# 01_MAIN.net
KiCad netlist of a schematic drawn in Altium Designer
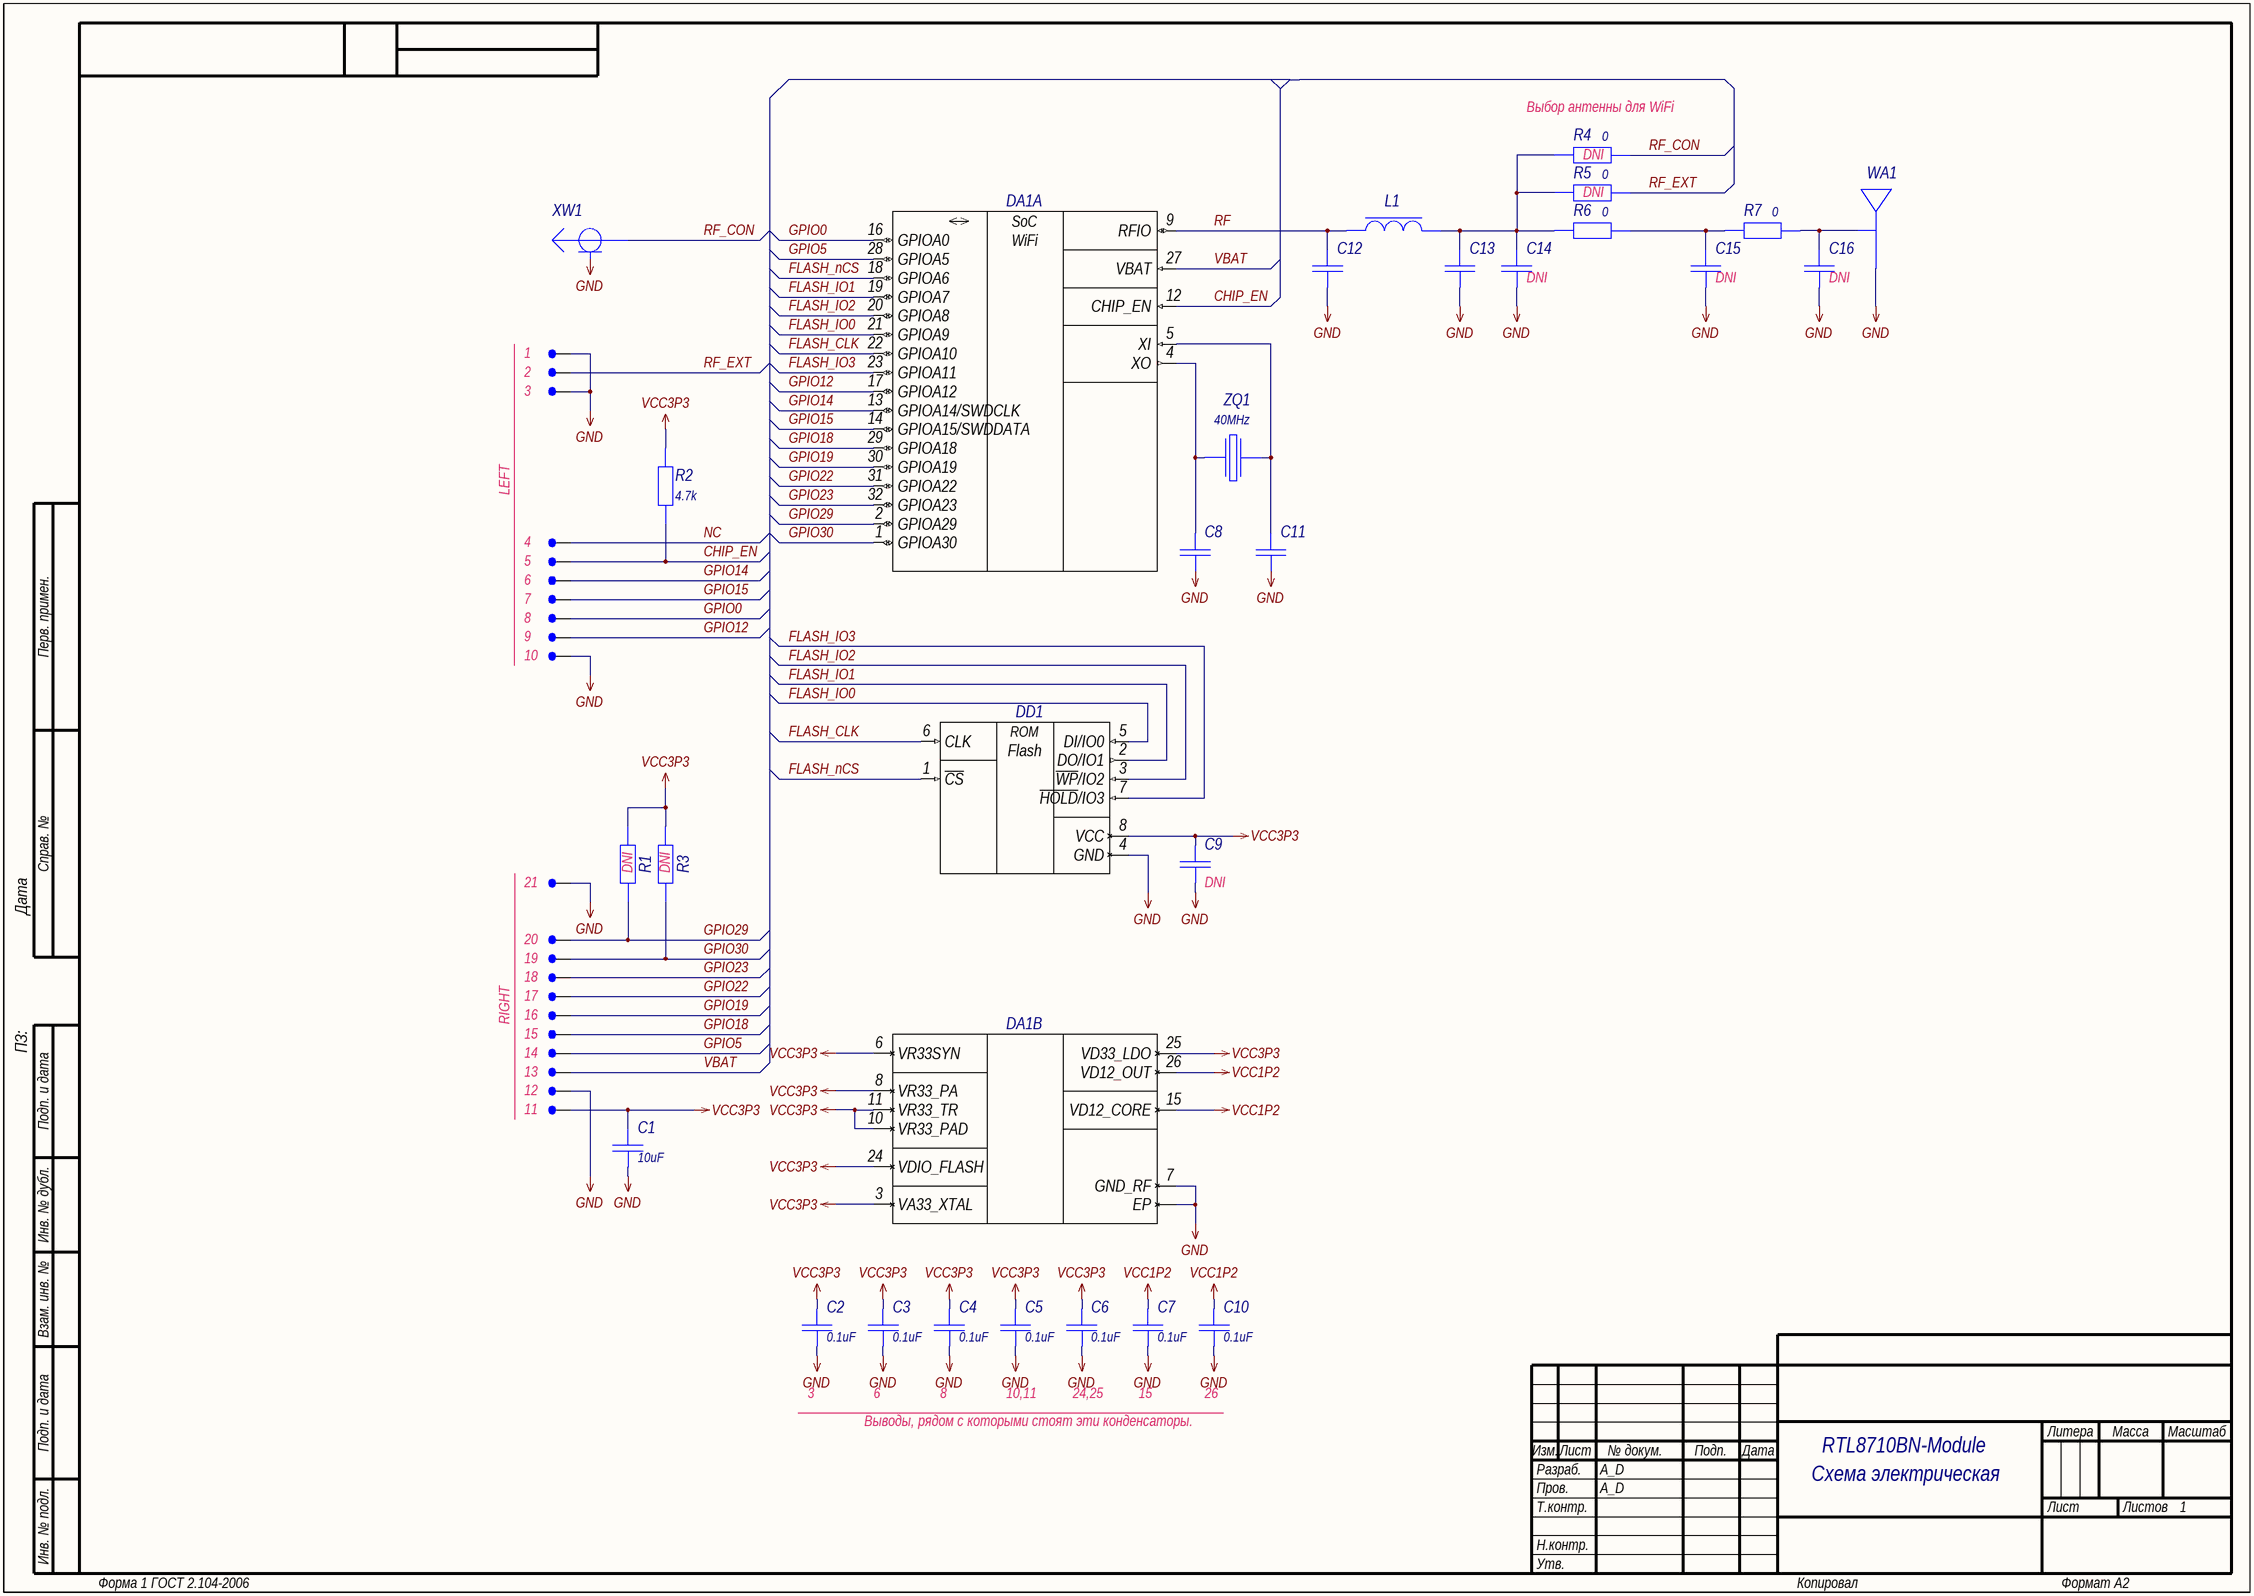
[diagram p0: 01_MAIN.SchDoc]

(export (version "E")
  (design (tool "Eeschema 10.0.6"))
  (components
    (comp (ref "C1")
      (value "10uF")
      (footprint "C0603_L")
      (fields
        (field (name "PART NUMBER") "GRM188R61A106KE69D")
        (field (name "VOLTAGE") "10V")
        (field (name "TOLERANCE") "±10%")
        (field (name "PUBLISHER") "Andrew Danich")
      )
      (libsource (lib "Lib_IMP_GOST") (part "Capacitor"))
    )
    (comp (ref "C2")
      (value "0.1uF")
      (footprint "C0402_L")
      (fields
        (field (name "PART NUMBER") "GRM155R71C104KA88D")
        (field (name "VOLTAGE") "16V")
        (field (name "TOLERANCE") "±10%")
        (field (name "PUBLISHER") "Andrew Danich")
      )
      (libsource (lib "Lib_IMP_GOST") (part "Capacitor"))
    )
    (comp (ref "C3")
      (value "0.1uF")
      (footprint "C0402_L")
      (fields
        (field (name "PART NUMBER") "GRM155R71C104KA88D")
        (field (name "VOLTAGE") "16V")
        (field (name "TOLERANCE") "±10%")
        (field (name "PUBLISHER") "Andrew Danich")
      )
      (libsource (lib "Lib_IMP_GOST") (part "Capacitor"))
    )
    (comp (ref "C4")
      (value "0.1uF")
      (footprint "C0402_L")
      (fields
        (field (name "PART NUMBER") "GRM155R71C104KA88D")
        (field (name "VOLTAGE") "16V")
        (field (name "TOLERANCE") "±10%")
        (field (name "PUBLISHER") "Andrew Danich")
      )
      (libsource (lib "Lib_IMP_GOST") (part "Capacitor"))
    )
    (comp (ref "C5")
      (value "0.1uF")
      (footprint "C0402_L")
      (fields
        (field (name "PART NUMBER") "GRM155R71C104KA88D")
        (field (name "VOLTAGE") "16V")
        (field (name "TOLERANCE") "±10%")
        (field (name "PUBLISHER") "Andrew Danich")
      )
      (libsource (lib "Lib_IMP_GOST") (part "Capacitor"))
    )
    (comp (ref "C6")
      (value "0.1uF")
      (footprint "C0402_L")
      (fields
        (field (name "PART NUMBER") "GRM155R71C104KA88D")
        (field (name "VOLTAGE") "16V")
        (field (name "TOLERANCE") "±10%")
        (field (name "PUBLISHER") "Andrew Danich")
      )
      (libsource (lib "Lib_IMP_GOST") (part "Capacitor"))
    )
    (comp (ref "C7")
      (value "0.1uF")
      (footprint "C0402_L")
      (fields
        (field (name "PART NUMBER") "GRM155R71C104KA88D")
        (field (name "VOLTAGE") "16V")
        (field (name "TOLERANCE") "±10%")
        (field (name "PUBLISHER") "Andrew Danich")
      )
      (libsource (lib "Lib_IMP_GOST") (part "Capacitor"))
    )
    (comp (ref "C8")
      (value "Capacitor")
      (footprint "C0402_L")
      (fields
        (field (name "PART NUMBER") "GRM1555C1H4R0CZ01D")
        (field (name "VOLTAGE") "50V")
        (field (name "TOLERANCE") "±0.25pF")
        (field (name "PUBLISHER") "Andrew Danich")
      )
      (libsource (lib "Lib_IMP_GOST") (part "Capacitor"))
    )
    (comp (ref "C9")
      (value "Capacitor")
      (footprint "C0402_L")
      (fields
        (field (name "PART NUMBER") "GRM155R71C104KA88D")
        (field (name "VOLTAGE") "16V")
        (field (name "TOLERANCE") "±10%")
        (field (name "PUBLISHER") "Andrew Danich")
      )
      (libsource (lib "Lib_IMP_GOST") (part "Capacitor"))
    )
    (comp (ref "C10")
      (value "0.1uF")
      (footprint "C0402_L")
      (fields
        (field (name "PART NUMBER") "GRM155R71C104KA88D")
        (field (name "VOLTAGE") "16V")
        (field (name "TOLERANCE") "±10%")
        (field (name "PUBLISHER") "Andrew Danich")
      )
      (libsource (lib "Lib_IMP_GOST") (part "Capacitor"))
    )
    (comp (ref "C11")
      (value "Capacitor")
      (footprint "C0402_L")
      (fields
        (field (name "PART NUMBER") "GRM1555C1H4R0CZ01D")
        (field (name "VOLTAGE") "50V")
        (field (name "TOLERANCE") "±0.25pF")
        (field (name "PUBLISHER") "Andrew Danich")
      )
      (libsource (lib "Lib_IMP_GOST") (part "Capacitor"))
    )
    (comp (ref "C12")
      (value "Capacitor")
      (footprint "C0402_L")
      (fields
        (field (name "PART NUMBER") "GRM1555C1H100JA01D")
        (field (name "VOLTAGE") "50V")
        (field (name "TOLERANCE") "±5%")
        (field (name "PUBLISHER") "Andrew Danich")
      )
      (libsource (lib "Lib_IMP_GOST") (part "Capacitor"))
    )
    (comp (ref "C13")
      (value "Capacitor")
      (footprint "C0402_L")
      (fields
        (field (name "PART NUMBER") "GRM1555C1H100JA01D")
        (field (name "VOLTAGE") "50V")
        (field (name "TOLERANCE") "±5%")
        (field (name "PUBLISHER") "Andrew Danich")
      )
      (libsource (lib "Lib_IMP_GOST") (part "Capacitor"))
    )
    (comp (ref "C14")
      (value "Capacitor")
      (footprint "C0402_L")
      (fields
        (field (name "PART NUMBER") "GRM1555C1H100JA01D")
        (field (name "VOLTAGE") "50V")
        (field (name "TOLERANCE") "±5%")
        (field (name "PUBLISHER") "Andrew Danich")
      )
      (libsource (lib "Lib_IMP_GOST") (part "Capacitor"))
    )
    (comp (ref "C15")
      (value "Capacitor")
      (footprint "C0402_L")
      (fields
        (field (name "PART NUMBER") "GRM1555C1H100JA01D")
        (field (name "VOLTAGE") "50V")
        (field (name "TOLERANCE") "±5%")
        (field (name "PUBLISHER") "Andrew Danich")
      )
      (libsource (lib "Lib_IMP_GOST") (part "Capacitor"))
    )
    (comp (ref "C16")
      (value "Capacitor")
      (footprint "C0402_L")
      (fields
        (field (name "PART NUMBER") "GRM1555C1H100JA01D")
        (field (name "VOLTAGE") "50V")
        (field (name "TOLERANCE") "±5%")
        (field (name "PUBLISHER") "Andrew Danich")
      )
      (libsource (lib "Lib_IMP_GOST") (part "Capacitor"))
    )
    (comp (ref "DA1")
      (value "RTL8710BN")
      (footprint "QFN-32")
      (fields (field (name "MANUFACTURER") "Realtek") (field (name "PUBLISHER") "Andrew Danich"))
      (libsource (lib "Lib_IMP_GOST") (part "RTL8710BN"))
    )
    (comp (ref "DD1")
      (value "W25Q-Series")
      (footprint "SOIC-8")
      (fields
        (field (name "PART NUMBER") "W25Q16DVSNIG")
        (field (name "MANUFACTURER") "Winbond")
        (field (name "PUBLISHER") "Andrew Danich")
      )
      (libsource (lib "Lib_IMP_GOST") (part "W25Q-Series"))
    )
    (comp (ref "L1")
      (value "Coil")
      (footprint "L0402_L")
      (fields
        (field (name "PART NUMBER") "LQG15HS2N2S02D")
        (field (name "TOLERANCE") "±0.3nH")
        (field (name "MANUFACTURER") "Murata")
        (field (name "PUBLISHER") "Andrew Danich")
      )
      (libsource (lib "Lib_IMP_GOST") (part "Coil"))
    )
    (comp (ref "R1")
      (value "Resistor")
      (footprint "R0402_L")
      (fields
        (field (name "PART NUMBER") "RC0402JR-074K7L")
        (field (name "TOLERANCE") "±5%")
        (field (name "MANUFACTURER") "Yageo")
        (field (name "PUBLISHER") "Andrew Danich")
      )
      (libsource (lib "Lib_IMP_GOST") (part "Resistor"))
    )
    (comp (ref "R2")
      (value "4.7k")
      (footprint "R0402_L")
      (fields
        (field (name "PART NUMBER") "RC0402JR-074K7L")
        (field (name "TOLERANCE") "±5%")
        (field (name "MANUFACTURER") "Yageo")
        (field (name "PUBLISHER") "Andrew Danich")
      )
      (libsource (lib "Lib_IMP_GOST") (part "Resistor"))
    )
    (comp (ref "R3")
      (value "Resistor")
      (footprint "R0402_L")
      (fields
        (field (name "PART NUMBER") "RC0402JR-074K7L")
        (field (name "TOLERANCE") "±5%")
        (field (name "MANUFACTURER") "Yageo")
        (field (name "PUBLISHER") "Andrew Danich")
      )
      (libsource (lib "Lib_IMP_GOST") (part "Resistor"))
    )
    (comp (ref "R4")
      (value "0")
      (footprint "R0402_L")
      (fields
        (field (name "PART NUMBER") "RC0402JR-070RL")
        (field (name "TOLERANCE") "±1%")
        (field (name "MANUFACTURER") "Yageo")
        (field (name "PUBLISHER") "Andrew Danich")
      )
      (libsource (lib "Lib_IMP_GOST") (part "Resistor"))
    )
    (comp (ref "R5")
      (value "0")
      (footprint "R0402_L")
      (fields
        (field (name "PART NUMBER") "RC0402JR-070RL")
        (field (name "TOLERANCE") "±1%")
        (field (name "MANUFACTURER") "Yageo")
        (field (name "PUBLISHER") "Andrew Danich")
      )
      (libsource (lib "Lib_IMP_GOST") (part "Resistor"))
    )
    (comp (ref "R6")
      (value "0")
      (footprint "R0402_L")
      (fields
        (field (name "PART NUMBER") "RC0402JR-070RL")
        (field (name "TOLERANCE") "±1%")
        (field (name "MANUFACTURER") "Yageo")
        (field (name "PUBLISHER") "Andrew Danich")
      )
      (libsource (lib "Lib_IMP_GOST") (part "Resistor"))
    )
    (comp (ref "R7")
      (value "0")
      (footprint "R0402_L")
      (fields
        (field (name "PART NUMBER") "RC0402JR-070RL")
        (field (name "TOLERANCE") "±1%")
        (field (name "MANUFACTURER") "Yageo")
        (field (name "PUBLISHER") "Andrew Danich")
      )
      (libsource (lib "Lib_IMP_GOST") (part "Resistor"))
    )
    (comp (ref "WA1")
      (value "Antenna_PCB_2p")
      (footprint "PCB-AN043")
      (fields
        (field (name "PART NUMBER") "PCB-AN043")
        (field (name "MANUFACTURER") "Texas Instruments")
        (field (name "PUBLISHER") "Andrew Danich")
      )
      (libsource (lib "Lib_IMP_GOST") (part "Antenna_PCB_2p"))
    )
    (comp (ref "XS1") (value "PCB-SPIN") (footprint "PCB-SPIN") (libsource (lib "Schlib") (part "PCB-SPIN")))
    (comp (ref "XS2") (value "PCB-SPIN") (footprint "PCB-SPIN") (libsource (lib "Schlib") (part "PCB-SPIN")))
    (comp (ref "XS3") (value "PCB-SPIN") (footprint "PCB-SPIN") (libsource (lib "Schlib") (part "PCB-SPIN")))
    (comp (ref "XS4") (value "PCB-SPIN") (footprint "PCB-SPIN") (libsource (lib "Schlib") (part "PCB-SPIN")))
    (comp (ref "XS5") (value "PCB-SPIN") (footprint "PCB-SPIN") (libsource (lib "Schlib") (part "PCB-SPIN")))
    (comp (ref "XS6") (value "PCB-SPIN") (footprint "PCB-SPIN") (libsource (lib "Schlib") (part "PCB-SPIN")))
    (comp (ref "XS7") (value "PCB-SPIN") (footprint "PCB-SPIN") (libsource (lib "Schlib") (part "PCB-SPIN")))
    (comp (ref "XS8") (value "PCB-SPIN") (footprint "PCB-SPIN") (libsource (lib "Schlib") (part "PCB-SPIN")))
    (comp (ref "XS9") (value "PCB-SPIN") (footprint "PCB-SPIN") (libsource (lib "Schlib") (part "PCB-SPIN")))
    (comp (ref "XS10") (value "PCB-SPIN") (footprint "PCB-SPIN") (libsource (lib "Schlib") (part "PCB-SPIN")))
    (comp (ref "XS11") (value "PCB-SPIN") (footprint "PCB-SPIN") (libsource (lib "Schlib") (part "PCB-SPIN")))
    (comp (ref "XS12") (value "PCB-SPIN") (footprint "PCB-SPIN") (libsource (lib "Schlib") (part "PCB-SPIN")))
    (comp (ref "XS13") (value "PCB-SPIN") (footprint "PCB-SPIN") (libsource (lib "Schlib") (part "PCB-SPIN")))
    (comp (ref "XS14") (value "PCB-SPIN") (footprint "PCB-SPIN") (libsource (lib "Schlib") (part "PCB-SPIN")))
    (comp (ref "XS15") (value "PCB-SPIN") (footprint "PCB-SPIN") (libsource (lib "Schlib") (part "PCB-SPIN")))
    (comp (ref "XS16") (value "PCB-SPIN") (footprint "PCB-SPIN") (libsource (lib "Schlib") (part "PCB-SPIN")))
    (comp (ref "XS17") (value "PCB-SPIN") (footprint "PCB-SPIN") (libsource (lib "Schlib") (part "PCB-SPIN")))
    (comp (ref "XS18") (value "PCB-SPIN") (footprint "PCB-SPIN") (libsource (lib "Schlib") (part "PCB-SPIN")))
    (comp (ref "XS19") (value "PCB-SPIN") (footprint "PCB-SPIN") (libsource (lib "Schlib") (part "PCB-SPIN")))
    (comp (ref "XS20") (value "PCB-SPIN") (footprint "PCB-SPIN") (libsource (lib "Schlib") (part "PCB-SPIN")))
    (comp (ref "XS21") (value "PCB-SPIN") (footprint "PCB-SPIN") (libsource (lib "Schlib") (part "PCB-SPIN")))
    (comp (ref "XW1")
      (value "Con-RF-M")
      (footprint "1909763-1")
      (fields
        (field (name "PART NUMBER") "1909763-1")
        (field (name "MANUFACTURER") "TE Connectivity")
        (field (name "PUBLISHER") "НТЦ \"Вектор\"")
      )
      (libsource (lib "Lib_IMP_GOST") (part "Con-RF-M"))
    )
    (comp (ref "ZQ1")
      (value "Crystal")
      (footprint "SX-2520")
      (fields
        (field (name "PART NUMBER") "CX2520DB40000D0FLJCC")
        (field (name "OUTPUT FREQUENCY") "40MHz")
        (field (name "MANUFACTURER") "AVX / Kyocera")
        (field (name "PUBLISHER") "Andrew Danich")
      )
      (libsource (lib "Lib_IMP_GOST") (part "Crystal"))
    )
  )
  (nets
    (net (code "1") (name "/CHIP_EN") (class "Default")
      (node (ref "DA1") (pin "12") (pinfunction "CHIP_EN_12") (pintype "input"))
      (node (ref "R2") (pin "1") (pinfunction "1_1") (pintype "passive"))
      (node (ref "XS5") (pin "1") (pinfunction "1_1") (pintype "passive"))
    )
    (net (code "2") (name "/FLASH_CLK") (class "Default")
      (node (ref "DA1") (pin "22") (pinfunction "GPIOA10_22") (pintype "bidirectional"))
      (node (ref "DD1") (pin "6") (pinfunction "CLK_6") (pintype "input"))
    )
    (net (code "3") (name "/FLASH_IO0") (class "Default")
      (node (ref "DA1") (pin "21") (pinfunction "GPIOA9_21") (pintype "bidirectional"))
      (node (ref "DD1") (pin "5") (pinfunction "DI/IO0_5") (pintype "input"))
    )
    (net (code "4") (name "/FLASH_IO1") (class "Default")
      (node (ref "DA1") (pin "19") (pinfunction "GPIOA7_19") (pintype "bidirectional"))
      (node (ref "DD1") (pin "2") (pinfunction "DO/IO1_2") (pintype "output"))
    )
    (net (code "5") (name "/FLASH_IO2") (class "Default")
      (node (ref "DA1") (pin "20") (pinfunction "GPIOA8_20") (pintype "bidirectional"))
      (node (ref "DD1") (pin "3") (pinfunction "~{WP}/IO2_3") (pintype "input"))
    )
    (net (code "6") (name "/FLASH_IO3") (class "Default")
      (node (ref "DA1") (pin "23") (pinfunction "GPIOA11_23") (pintype "bidirectional"))
      (node (ref "DD1") (pin "7") (pinfunction "~{HOLD}/IO3_7") (pintype "input"))
    )
    (net (code "7") (name "/FLASH_nCS") (class "Default")
      (node (ref "DA1") (pin "18") (pinfunction "GPIOA6_18") (pintype "bidirectional"))
      (node (ref "DD1") (pin "1") (pinfunction "~{CS}_1") (pintype "input"))
    )
    (net (code "8") (name "/GPIO0") (class "Default")
      (node (ref "DA1") (pin "16") (pinfunction "GPIOA0_16") (pintype "bidirectional"))
      (node (ref "XS8") (pin "1") (pinfunction "1_1") (pintype "passive"))
    )
    (net (code "9") (name "/GPIO5") (class "Default")
      (node (ref "DA1") (pin "28") (pinfunction "GPIOA5_28") (pintype "bidirectional"))
      (node (ref "XS18") (pin "1") (pinfunction "1_1") (pintype "passive"))
    )
    (net (code "10") (name "/GPIO12") (class "Default")
      (node (ref "DA1") (pin "17") (pinfunction "GPIOA12_17") (pintype "bidirectional"))
      (node (ref "XS9") (pin "1") (pinfunction "1_1") (pintype "passive"))
    )
    (net (code "11") (name "/GPIO14") (class "Default")
      (node (ref "DA1") (pin "13") (pinfunction "GPIOA14/SWDCLK_13") (pintype "bidirectional"))
      (node (ref "XS6") (pin "1") (pinfunction "1_1") (pintype "passive"))
    )
    (net (code "12") (name "/GPIO15") (class "Default")
      (node (ref "DA1") (pin "14") (pinfunction "GPIOA15/SWDDATA_14") (pintype "bidirectional"))
      (node (ref "XS7") (pin "1") (pinfunction "1_1") (pintype "passive"))
    )
    (net (code "13") (name "/GPIO18") (class "Default")
      (node (ref "DA1") (pin "29") (pinfunction "GPIOA18_29") (pintype "bidirectional"))
      (node (ref "XS17") (pin "1") (pinfunction "1_1") (pintype "passive"))
    )
    (net (code "14") (name "/GPIO19") (class "Default")
      (node (ref "DA1") (pin "30") (pinfunction "GPIOA19_30") (pintype "bidirectional"))
      (node (ref "XS16") (pin "1") (pinfunction "1_1") (pintype "passive"))
    )
    (net (code "15") (name "/GPIO22") (class "Default")
      (node (ref "DA1") (pin "31") (pinfunction "GPIOA22_31") (pintype "bidirectional"))
      (node (ref "XS15") (pin "1") (pinfunction "1_1") (pintype "passive"))
    )
    (net (code "16") (name "/GPIO23") (class "Default")
      (node (ref "DA1") (pin "32") (pinfunction "GPIOA23_32") (pintype "bidirectional"))
      (node (ref "XS14") (pin "1") (pinfunction "1_1") (pintype "passive"))
    )
    (net (code "17") (name "/GPIO29") (class "Default")
      (node (ref "DA1") (pin "2") (pinfunction "GPIOA29_2") (pintype "bidirectional"))
      (node (ref "R1") (pin "1") (pinfunction "1_1") (pintype "passive"))
      (node (ref "XS12") (pin "1") (pinfunction "1_1") (pintype "passive"))
    )
    (net (code "18") (name "/GPIO30") (class "Default")
      (node (ref "DA1") (pin "1") (pinfunction "GPIOA30_1") (pintype "bidirectional"))
      (node (ref "R3") (pin "1") (pinfunction "1_1") (pintype "passive"))
      (node (ref "XS13") (pin "1") (pinfunction "1_1") (pintype "passive"))
    )
    (net (code "19") (name "/NC") (class "Default")
      (node (ref "XS4") (pin "1") (pinfunction "1_1") (pintype "passive"))
    )
    (net (code "20") (name "/RF") (class "Default")
      (node (ref "C12") (pin "2") (pinfunction "2_2") (pintype "passive"))
      (node (ref "DA1") (pin "9") (pinfunction "RFIO_9") (pintype "bidirectional"))
      (node (ref "L1") (pin "1") (pinfunction "1_1") (pintype "passive"))
    )
    (net (code "21") (name "/RF_CON") (class "Default")
      (node (ref "R4") (pin "2") (pinfunction "2_2") (pintype "passive"))
      (node (ref "XW1") (pin "1") (pintype "passive"))
    )
    (net (code "22") (name "/RF_EXT") (class "Default")
      (node (ref "R5") (pin "2") (pinfunction "2_2") (pintype "passive"))
      (node (ref "XS2") (pin "1") (pinfunction "1_1") (pintype "passive"))
    )
    (net (code "23") (name "/VBAT") (class "Default")
      (node (ref "DA1") (pin "27") (pinfunction "VBAT_27") (pintype "input"))
      (node (ref "XS19") (pin "1") (pinfunction "1_1") (pintype "passive"))
    )
    (net (code "24") (name "GND") (class "Default")
      (node (ref "C1") (pin "1") (pinfunction "1_1") (pintype "passive"))
      (node (ref "C10") (pin "1") (pinfunction "1_1") (pintype "passive"))
      (node (ref "C11") (pin "1") (pinfunction "1_1") (pintype "passive"))
      (node (ref "C12") (pin "1") (pinfunction "1_1") (pintype "passive"))
      (node (ref "C13") (pin "1") (pinfunction "1_1") (pintype "passive"))
      (node (ref "C14") (pin "1") (pinfunction "1_1") (pintype "passive"))
      (node (ref "C15") (pin "1") (pinfunction "1_1") (pintype "passive"))
      (node (ref "C16") (pin "1") (pinfunction "1_1") (pintype "passive"))
      (node (ref "C2") (pin "1") (pinfunction "1_1") (pintype "passive"))
      (node (ref "C3") (pin "1") (pinfunction "1_1") (pintype "passive"))
      (node (ref "C4") (pin "1") (pinfunction "1_1") (pintype "passive"))
      (node (ref "C5") (pin "1") (pinfunction "1_1") (pintype "passive"))
      (node (ref "C6") (pin "1") (pinfunction "1_1") (pintype "passive"))
      (node (ref "C7") (pin "1") (pinfunction "1_1") (pintype "passive"))
      (node (ref "C8") (pin "1") (pinfunction "1_1") (pintype "passive"))
      (node (ref "C9") (pin "1") (pinfunction "1_1") (pintype "passive"))
      (node (ref "DA1") (pin "33") (pinfunction "EP_33") (pintype "power_in"))
      (node (ref "DA1") (pin "7") (pinfunction "GND_RF_7") (pintype "power_in"))
      (node (ref "DD1") (pin "4") (pinfunction "GND_4") (pintype "power_in"))
      (node (ref "WA1") (pin "2") (pinfunction "2_2") (pintype "passive"))
      (node (ref "XS1") (pin "1") (pinfunction "1_1") (pintype "passive"))
      (node (ref "XS10") (pin "1") (pinfunction "1_1") (pintype "passive"))
      (node (ref "XS11") (pin "1") (pinfunction "1_1") (pintype "passive"))
      (node (ref "XS20") (pin "1") (pinfunction "1_1") (pintype "passive"))
      (node (ref "XS3") (pin "1") (pinfunction "1_1") (pintype "passive"))
      (node (ref "XW1") (pin "2") (pintype "passive"))
    )
    (net (code "25") (name "Net-(C13-Pad2)") (class "Default")
      (node (ref "C13") (pin "2") (pinfunction "2_2") (pintype "passive"))
      (node (ref "C14") (pin "2") (pinfunction "2_2") (pintype "passive"))
      (node (ref "L1") (pin "2") (pinfunction "2_2") (pintype "passive"))
      (node (ref "R4") (pin "1") (pinfunction "1_1") (pintype "passive"))
      (node (ref "R5") (pin "1") (pinfunction "1_1") (pintype "passive"))
      (node (ref "R6") (pin "1") (pinfunction "1_1") (pintype "passive"))
    )
    (net (code "26") (name "Net-(C15-Pad2)") (class "Default")
      (node (ref "C15") (pin "2") (pinfunction "2_2") (pintype "passive"))
      (node (ref "R6") (pin "2") (pinfunction "2_2") (pintype "passive"))
      (node (ref "R7") (pin "1") (pinfunction "1_1") (pintype "passive"))
    )
    (net (code "27") (name "Net-(C16-Pad2)") (class "Default")
      (node (ref "C16") (pin "2") (pinfunction "2_2") (pintype "passive"))
      (node (ref "R7") (pin "2") (pinfunction "2_2") (pintype "passive"))
      (node (ref "WA1") (pin "1") (pinfunction "1_1") (pintype "passive"))
    )
    (net (code "28") (name "Net-(DA1A-XI)") (class "Default")
      (node (ref "C11") (pin "2") (pinfunction "2_2") (pintype "passive"))
      (node (ref "DA1") (pin "5") (pinfunction "XI_5") (pintype "input"))
      (node (ref "ZQ1") (pin "3") (pinfunction "3_3") (pintype "passive"))
    )
    (net (code "29") (name "Net-(DA1A-XO)") (class "Default")
      (node (ref "C8") (pin "2") (pinfunction "2_2") (pintype "passive"))
      (node (ref "DA1") (pin "4") (pinfunction "XO_4") (pintype "output"))
      (node (ref "ZQ1") (pin "1") (pinfunction "1_1") (pintype "passive"))
    )
    (net (code "30") (name "VCC1P2") (class "Default")
      (node (ref "C10") (pin "2") (pinfunction "2_2") (pintype "passive"))
      (node (ref "C7") (pin "2") (pinfunction "2_2") (pintype "passive"))
      (node (ref "DA1") (pin "15") (pinfunction "VD12_CORE_15") (pintype "power_in"))
      (node (ref "DA1") (pin "26") (pinfunction "VD12_OUT_26") (pintype "power_in"))
    )
    (net (code "31") (name "VCC3P3") (class "Default")
      (node (ref "C1") (pin "2") (pinfunction "2_2") (pintype "passive"))
      (node (ref "C2") (pin "2") (pinfunction "2_2") (pintype "passive"))
      (node (ref "C3") (pin "2") (pinfunction "2_2") (pintype "passive"))
      (node (ref "C4") (pin "2") (pinfunction "2_2") (pintype "passive"))
      (node (ref "C5") (pin "2") (pinfunction "2_2") (pintype "passive"))
      (node (ref "C6") (pin "2") (pinfunction "2_2") (pintype "passive"))
      (node (ref "C9") (pin "2") (pinfunction "2_2") (pintype "passive"))
      (node (ref "DA1") (pin "10") (pinfunction "VR33_PAD_10") (pintype "power_in"))
      (node (ref "DA1") (pin "11") (pinfunction "VR33_TR_11") (pintype "power_in"))
      (node (ref "DA1") (pin "24") (pinfunction "VDIO_FLASH_24") (pintype "power_in"))
      (node (ref "DA1") (pin "25") (pinfunction "VD33_LDO_25") (pintype "power_in"))
      (node (ref "DA1") (pin "3") (pinfunction "VA33_XTAL_3") (pintype "power_in"))
      (node (ref "DA1") (pin "6") (pinfunction "VR33SYN_6") (pintype "power_in"))
      (node (ref "DA1") (pin "8") (pinfunction "VR33_PA_8") (pintype "power_in"))
      (node (ref "DD1") (pin "8") (pinfunction "VCC_8") (pintype "power_in"))
      (node (ref "R1") (pin "2") (pinfunction "2_2") (pintype "passive"))
      (node (ref "R2") (pin "2") (pinfunction "2_2") (pintype "passive"))
      (node (ref "R3") (pin "2") (pinfunction "2_2") (pintype "passive"))
      (node (ref "XS21") (pin "1") (pinfunction "1_1") (pintype "passive"))
    )
  )
)
